# miavita.net
KiCad netlist of a schematic drawn in EAGLE
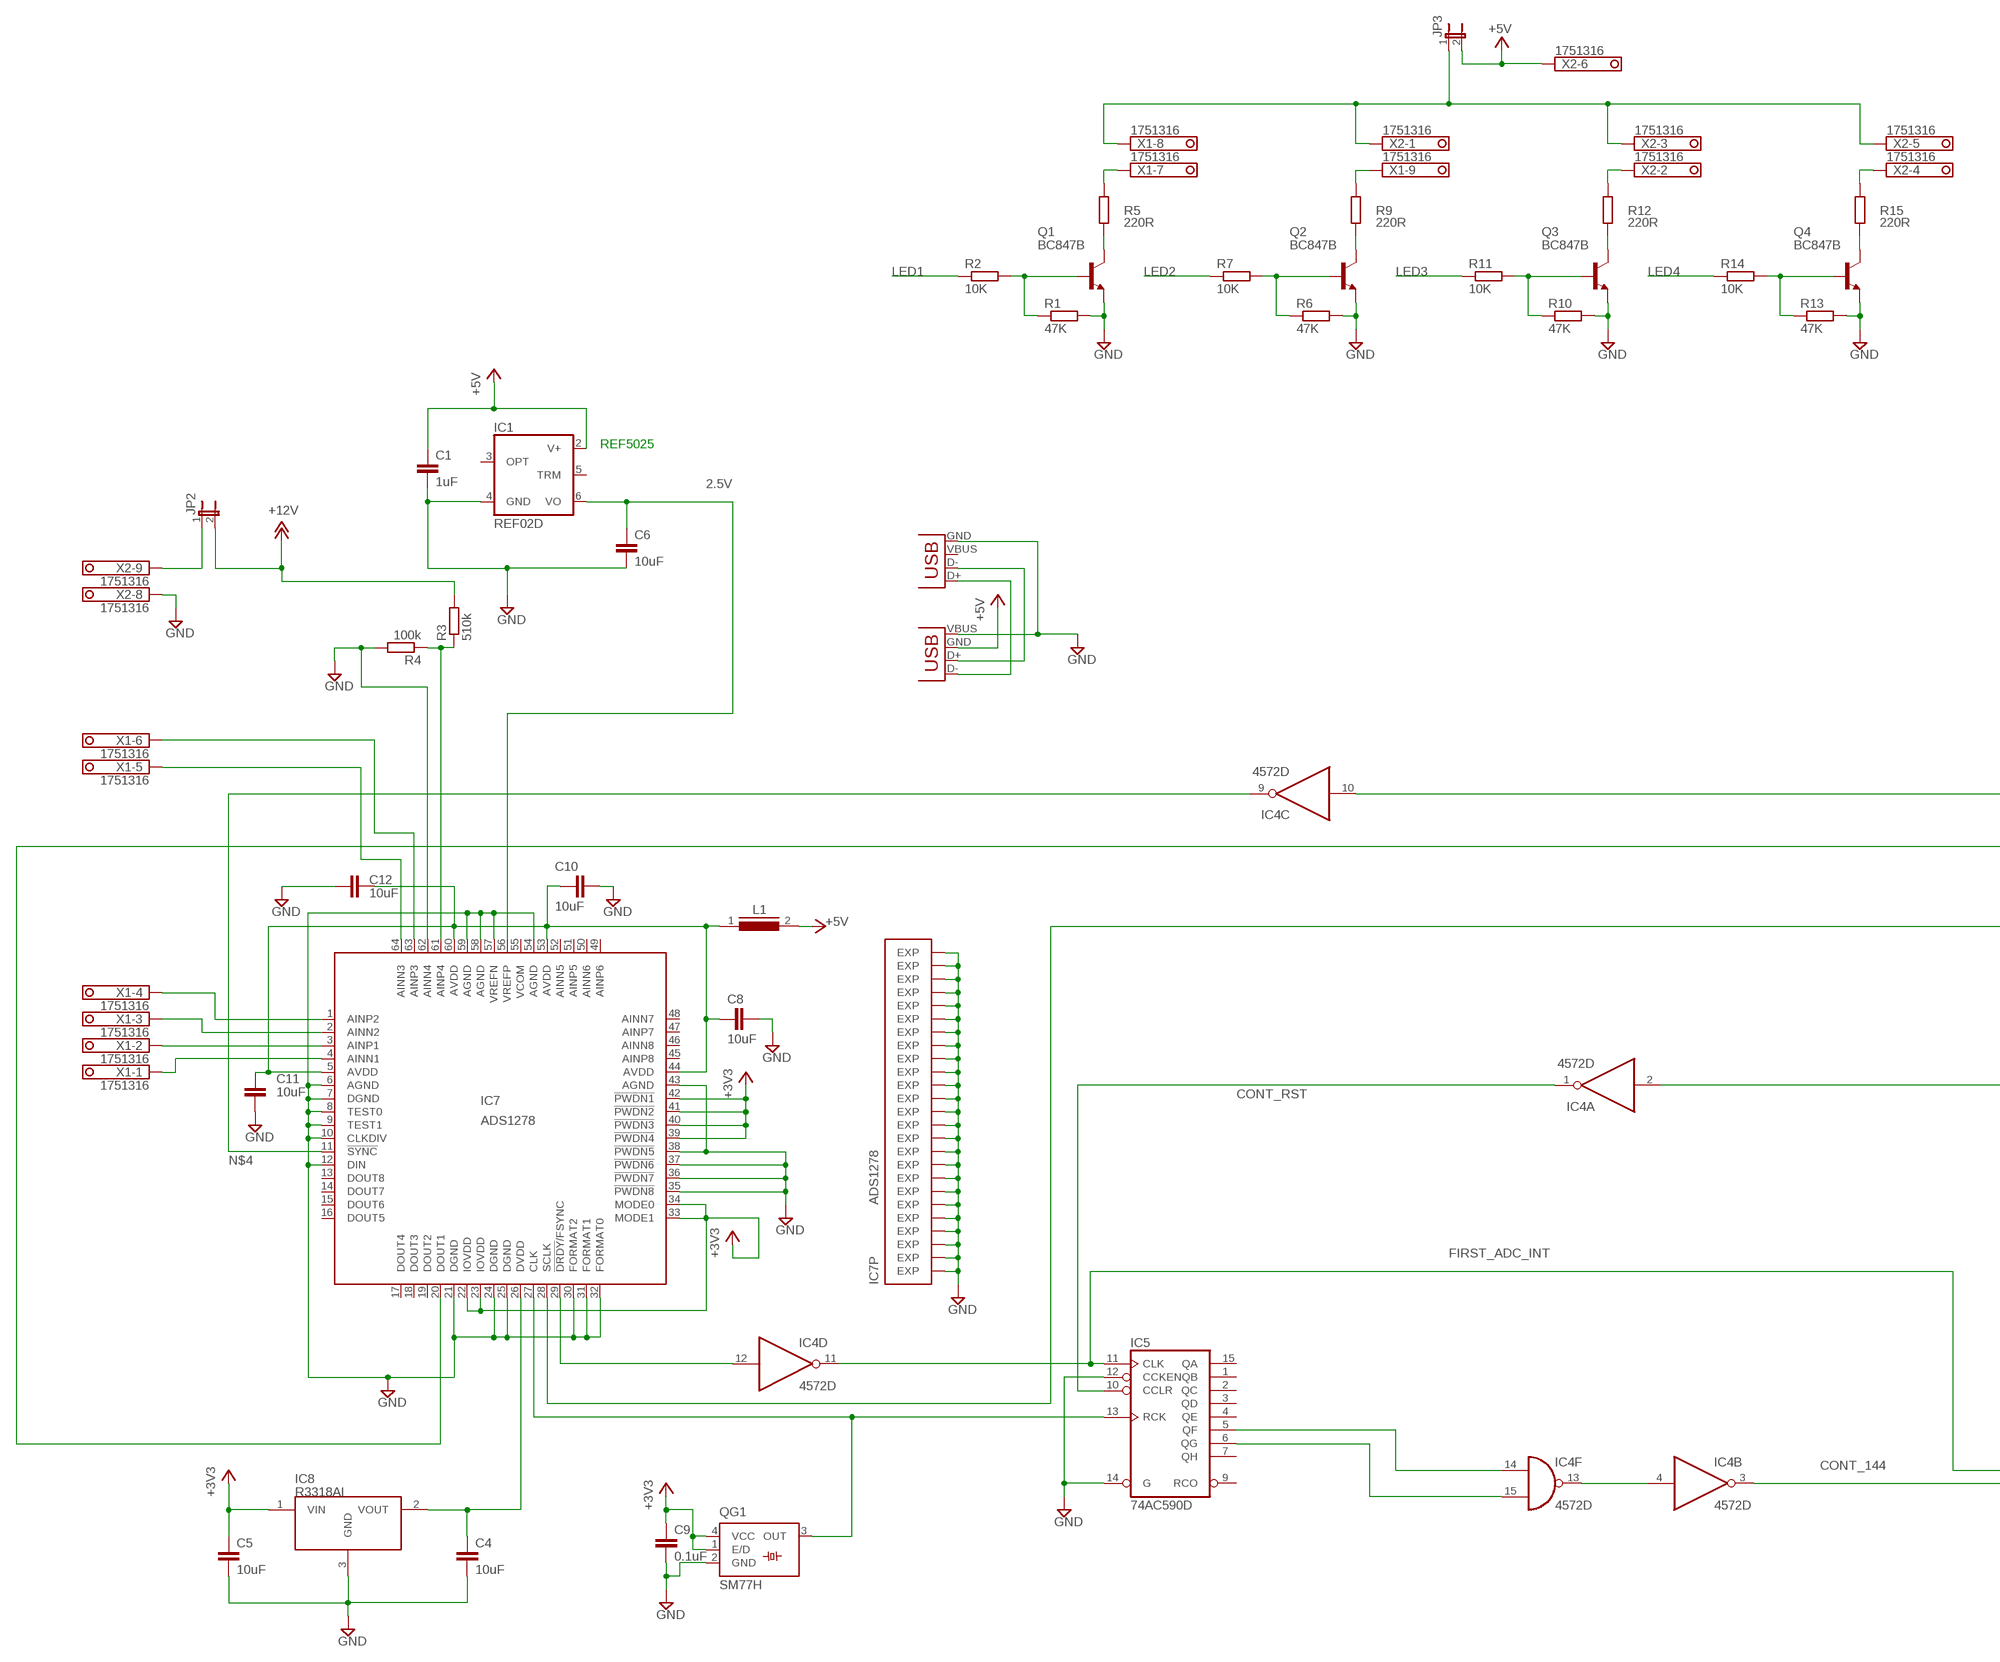
[diagram p0: schematic, sheet 1, part 1 of 2]
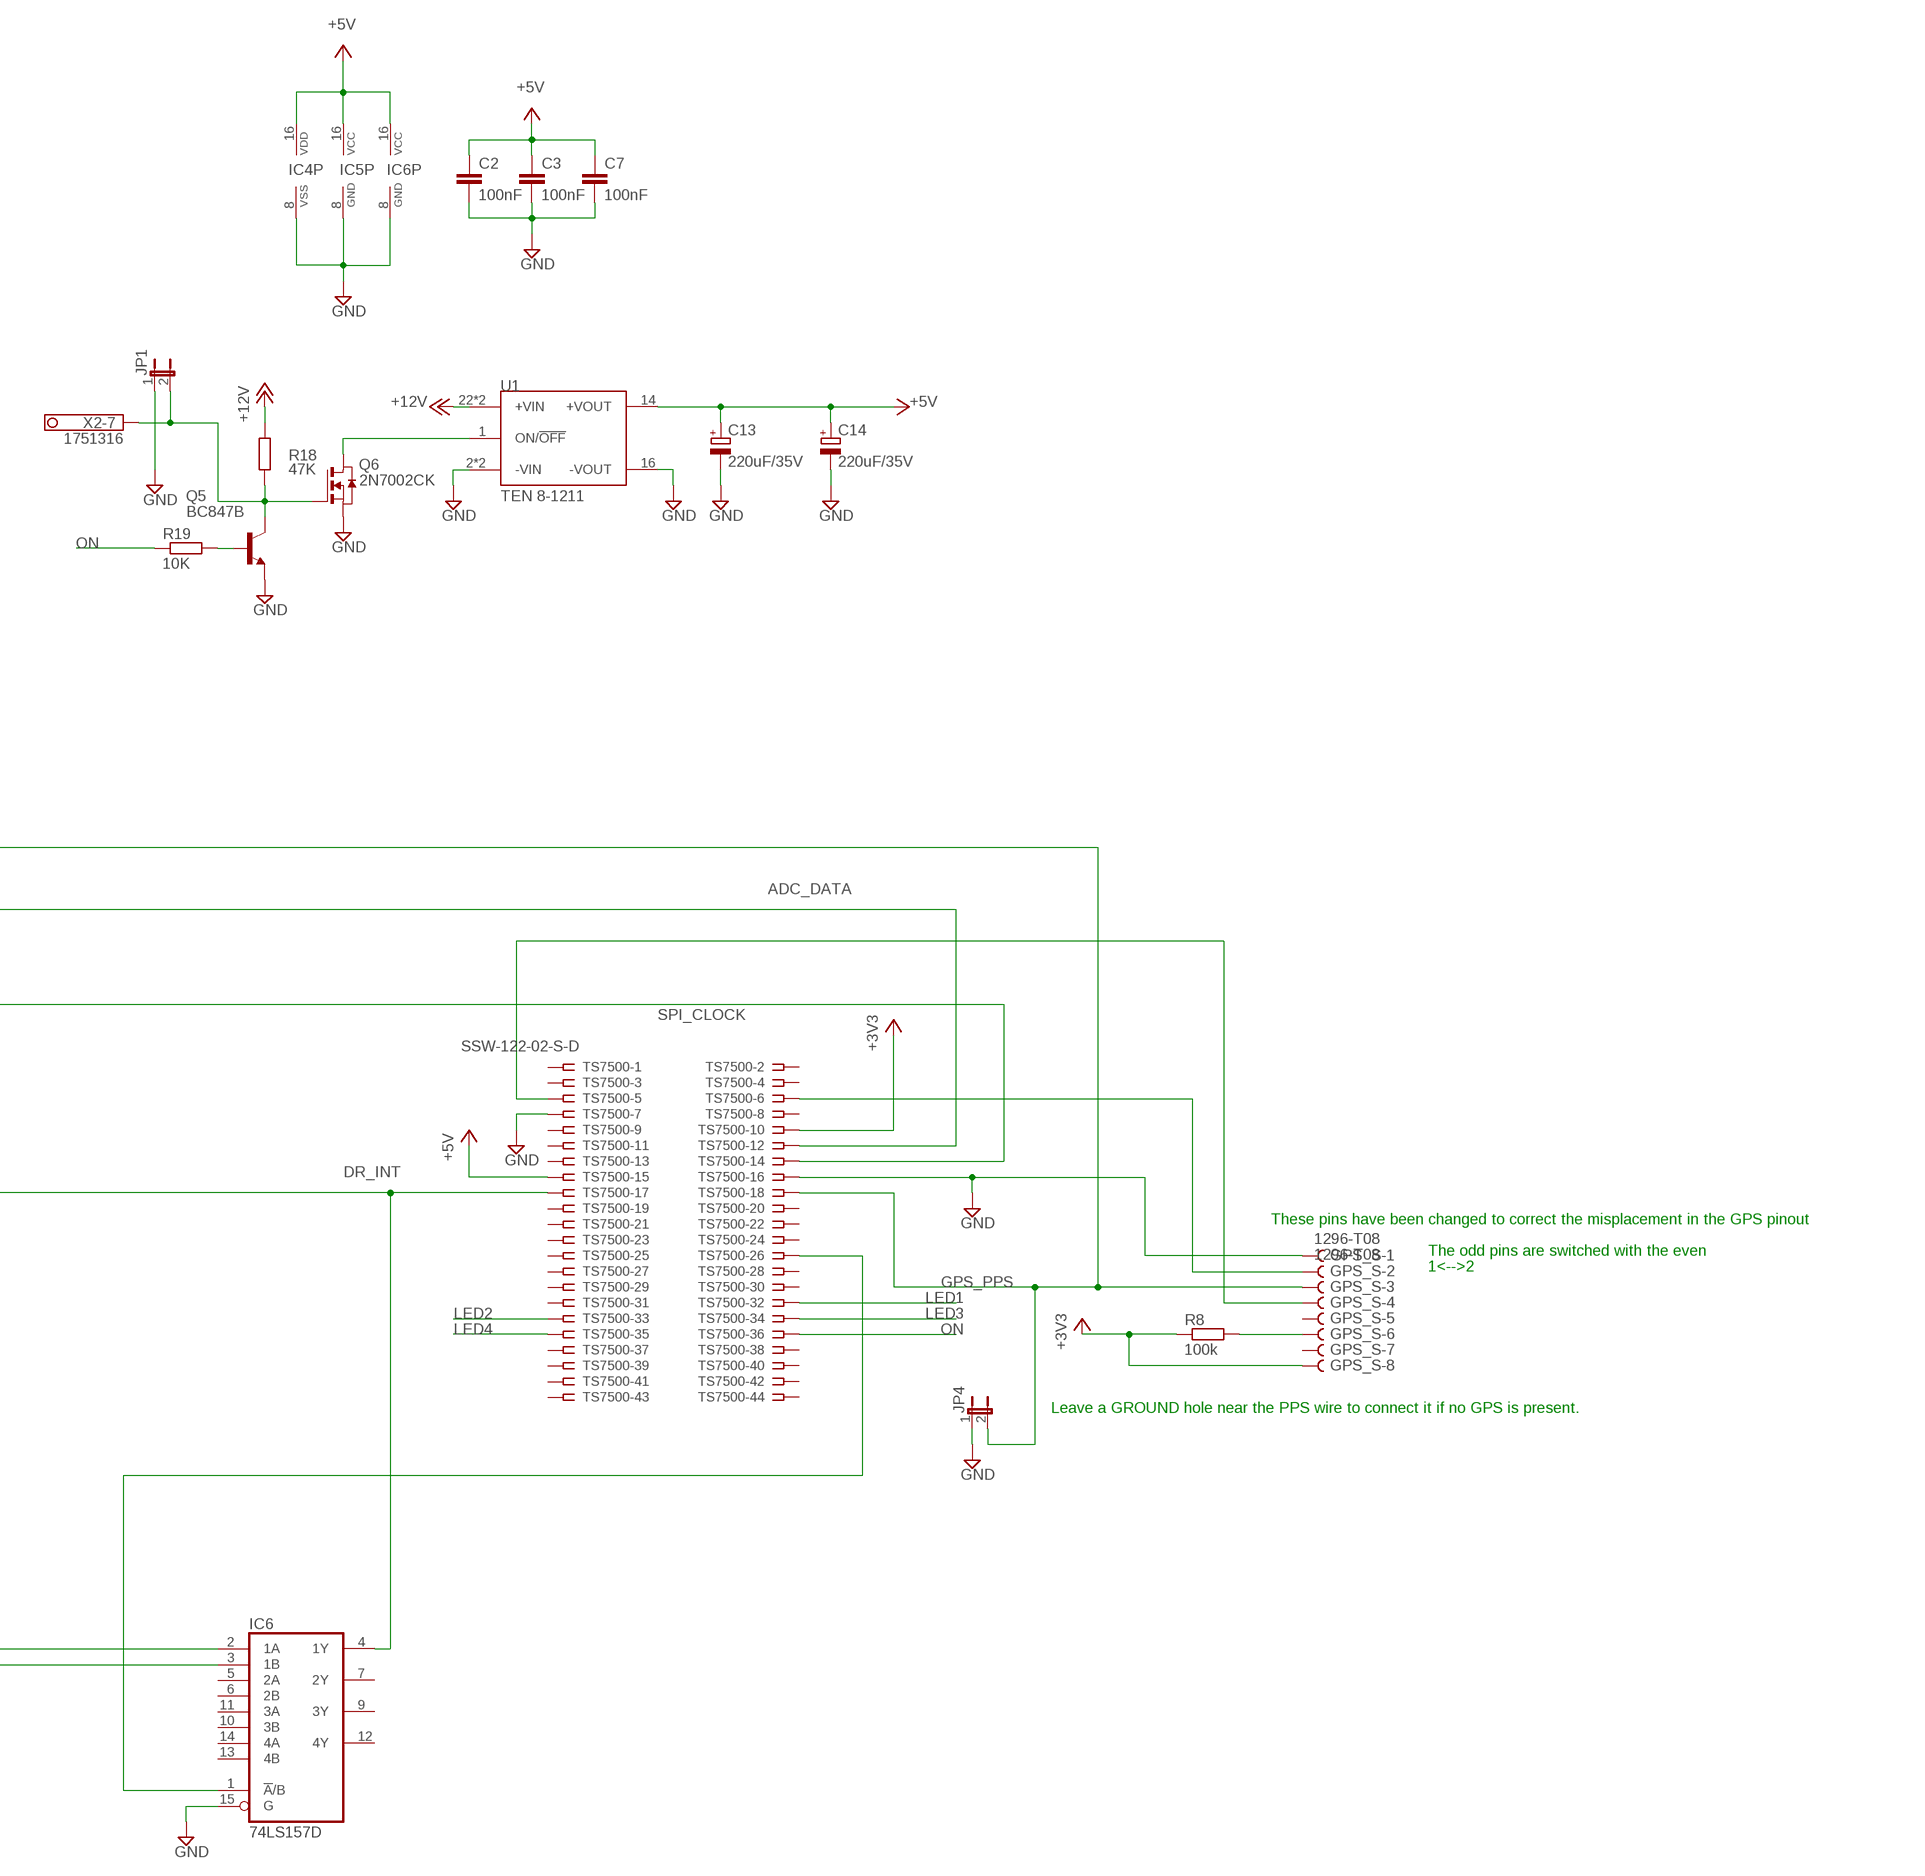
[diagram p1: schematic, sheet 1, part 2 of 2]

(export (version "E")
  (design (tool "Eeschema 10.0.6"))
  (components
    (comp (ref "C1")
      (value "1uF")
      (footprint "eagle-import:C0603")
      (libsource (lib "eagle-import") (part "C-EUC0603"))
    )
    (comp (ref "C2")
      (value "100nF")
      (footprint "eagle-import:C0603")
      (libsource (lib "eagle-import") (part "C-EUC0603"))
    )
    (comp (ref "C3")
      (value "100nF")
      (footprint "eagle-import:C0603")
      (libsource (lib "eagle-import") (part "C-EUC0603"))
    )
    (comp (ref "C4")
      (value "10uF")
      (footprint "eagle-import:C1210")
      (libsource (lib "eagle-import") (part "C-EUC1210"))
    )
    (comp (ref "C5")
      (value "10uF")
      (footprint "eagle-import:C1210")
      (libsource (lib "eagle-import") (part "C-EUC1210"))
    )
    (comp (ref "C6")
      (value "10uF")
      (footprint "eagle-import:C1210")
      (libsource (lib "eagle-import") (part "C-EUC1210"))
    )
    (comp (ref "C7")
      (value "100nF")
      (footprint "eagle-import:C0603")
      (libsource (lib "eagle-import") (part "C-EUC0603"))
    )
    (comp (ref "C8")
      (value "10uF")
      (footprint "eagle-import:C0805")
      (libsource (lib "eagle-import") (part "C-EUC0805"))
    )
    (comp (ref "C9")
      (value "0.1uF")
      (footprint "eagle-import:C0603")
      (libsource (lib "eagle-import") (part "C-EUC0603"))
    )
    (comp (ref "C10")
      (value "10uF")
      (footprint "eagle-import:C0805")
      (libsource (lib "eagle-import") (part "C-EUC0805"))
    )
    (comp (ref "C11")
      (value "10uF")
      (footprint "eagle-import:C0805")
      (libsource (lib "eagle-import") (part "C-EUC0805"))
    )
    (comp (ref "C12")
      (value "10uF")
      (footprint "eagle-import:C0805")
      (libsource (lib "eagle-import") (part "C-EUC0805"))
    )
    (comp (ref "C13")
      (value "220uF/35V")
      (footprint "eagle-import:UD-10X10_NICHICON")
      (libsource (lib "eagle-import") (part "CPOL-EUUD-10X10"))
    )
    (comp (ref "C14")
      (value "220uF/35V")
      (footprint "eagle-import:UD-10X10_NICHICON")
      (libsource (lib "eagle-import") (part "CPOL-EUUD-10X10"))
    )
    (comp (ref "GPS_S")
      (value "1296-T08")
      (footprint "eagle-import:1296-08")
      (libsource (lib "eagle-import") (part "1296-T08"))
    )
    (comp (ref "IC1")
      (value "REF02D")
      (footprint "eagle-import:SO08")
      (libsource (lib "eagle-import") (part "REF02D"))
    )
    (comp (ref "IC4")
      (value "4572D")
      (footprint "eagle-import:SO16")
      (libsource (lib "eagle-import") (part "4572D"))
    )
    (comp (ref "IC5")
      (value "74AC590D")
      (footprint "eagle-import:SO16")
      (libsource (lib "eagle-import") (part "74590DAC"))
    )
    (comp (ref "IC6")
      (value "74LS157D")
      (footprint "eagle-import:SO16")
      (libsource (lib "eagle-import") (part "74157DLS"))
    )
    (comp (ref "IC7")
      (value "ADS1278")
      (footprint "eagle-import:HTQFP-64-PAP")
      (fields (field (name "MPN") "ADS1278IPAPT"))
      (libsource (lib "eagle-import") (part "ADS1278"))
    )
    (comp (ref "IC8")
      (value "R3318AI")
      (footprint "eagle-import:SOT23")
      (libsource (lib "eagle-import") (part "MCP1525TTT-I/"))
    )
    (comp (ref "JP1")
      (value "JP1E")
      (footprint "eagle-import:JP1")
      (libsource (lib "eagle-import") (part "JP1E"))
    )
    (comp (ref "JP2")
      (value "JP1E")
      (footprint "eagle-import:JP1")
      (libsource (lib "eagle-import") (part "JP1E"))
    )
    (comp (ref "JP3")
      (value "JP1E")
      (footprint "eagle-import:JP1")
      (libsource (lib "eagle-import") (part "JP1E"))
    )
    (comp (ref "JP4")
      (value "JP1E")
      (footprint "eagle-import:JP1")
      (libsource (lib "eagle-import") (part "JP1E"))
    )
    (comp (ref "L1")
      (value "FAIR-RITE_2506031027Y0")
      (footprint "eagle-import:L0603")
      (libsource (lib "eagle-import") (part "FAIR-RITE_251027Y00603"))
    )
    (comp (ref "Q1")
      (value "BC847B")
      (footprint "eagle-import:SOT23")
      (libsource (lib "eagle-import") (part "BC847SMDBLT1"))
    )
    (comp (ref "Q2")
      (value "BC847B")
      (footprint "eagle-import:SOT23")
      (libsource (lib "eagle-import") (part "BC847SMDBLT1"))
    )
    (comp (ref "Q3")
      (value "BC847B")
      (footprint "eagle-import:SOT23")
      (libsource (lib "eagle-import") (part "BC847SMDBLT1"))
    )
    (comp (ref "Q4")
      (value "BC847B")
      (footprint "eagle-import:SOT23")
      (libsource (lib "eagle-import") (part "BC847SMDBLT1"))
    )
    (comp (ref "Q5")
      (value "BC847B")
      (footprint "eagle-import:SOT23")
      (libsource (lib "eagle-import") (part "BC847SMDBLT1"))
    )
    (comp (ref "Q6")
      (value "2N7002CK")
      (footprint "eagle-import:SOT23")
      (libsource (lib "eagle-import") (part "2N7002CK"))
    )
    (comp (ref "QG1")
      (value "SM77H")
      (footprint "eagle-import:SM77H")
      (libsource (lib "eagle-import") (part "SM77H"))
    )
    (comp (ref "R1")
      (value "47K")
      (footprint "eagle-import:R0603")
      (libsource (lib "eagle-import") (part "R-EU_R0603"))
    )
    (comp (ref "R2")
      (value "10K")
      (footprint "eagle-import:R0603")
      (libsource (lib "eagle-import") (part "R-EU_R0603"))
    )
    (comp (ref "R3")
      (value "510k")
      (footprint "eagle-import:R0603")
      (libsource (lib "eagle-import") (part "R-EU_R0603"))
    )
    (comp (ref "R4")
      (value "100k")
      (footprint "eagle-import:R0603")
      (libsource (lib "eagle-import") (part "R-EU_R0603"))
    )
    (comp (ref "R5")
      (value "220R")
      (footprint "eagle-import:R0603")
      (libsource (lib "eagle-import") (part "R-EU_R0603"))
    )
    (comp (ref "R6")
      (value "47K")
      (footprint "eagle-import:R0603")
      (libsource (lib "eagle-import") (part "R-EU_R0603"))
    )
    (comp (ref "R7")
      (value "10K")
      (footprint "eagle-import:R0603")
      (libsource (lib "eagle-import") (part "R-EU_R0603"))
    )
    (comp (ref "R8")
      (value "100k")
      (footprint "eagle-import:R0603")
      (libsource (lib "eagle-import") (part "R-EU_R0603"))
    )
    (comp (ref "R9")
      (value "220R")
      (footprint "eagle-import:R0603")
      (libsource (lib "eagle-import") (part "R-EU_R0603"))
    )
    (comp (ref "R10")
      (value "47K")
      (footprint "eagle-import:R0603")
      (libsource (lib "eagle-import") (part "R-EU_R0603"))
    )
    (comp (ref "R11")
      (value "10K")
      (footprint "eagle-import:R0603")
      (libsource (lib "eagle-import") (part "R-EU_R0603"))
    )
    (comp (ref "R12")
      (value "220R")
      (footprint "eagle-import:R0603")
      (libsource (lib "eagle-import") (part "R-EU_R0603"))
    )
    (comp (ref "R13")
      (value "47K")
      (footprint "eagle-import:R0603")
      (libsource (lib "eagle-import") (part "R-EU_R0603"))
    )
    (comp (ref "R14")
      (value "10K")
      (footprint "eagle-import:R0603")
      (libsource (lib "eagle-import") (part "R-EU_R0603"))
    )
    (comp (ref "R15")
      (value "220R")
      (footprint "eagle-import:R0603")
      (libsource (lib "eagle-import") (part "R-EU_R0603"))
    )
    (comp (ref "R18")
      (value "47K")
      (footprint "eagle-import:R0603")
      (libsource (lib "eagle-import") (part "R-EU_R0603"))
    )
    (comp (ref "R19")
      (value "10K")
      (footprint "eagle-import:R0603")
      (libsource (lib "eagle-import") (part "R-EU_R0603"))
    )
    (comp (ref "TS7500")
      (value "SSW-122-02-S-D")
      (footprint "eagle-import:SSW-122-02-S-D")
      (libsource (lib "eagle-import") (part "SSW-122-02-S-D"))
    )
    (comp (ref "U1")
      (value "TEN 8-1211")
      (footprint "eagle-import:TRACOPOWER_TEN-8-SERIES")
      (libsource (lib "eagle-import") (part "TRACOPOWER_TEN-8-1211"))
    )
    (comp (ref "USBA")
      (value "USB-A-H")
      (footprint "eagle-import:USB-A-H")
      (libsource (lib "eagle-import") (part "USB-A-H"))
    )
    (comp (ref "USBB")
      (value "USBPTH")
      (footprint "eagle-import:USB-B-PTH")
      (libsource (lib "eagle-import") (part "USBPTH"))
    )
    (comp (ref "X1")
      (value "1751316")
      (footprint "eagle-import:1751316")
      (libsource (lib "eagle-import") (part "1751316"))
    )
    (comp (ref "X2")
      (value "1751316")
      (footprint "eagle-import:1751316")
      (libsource (lib "eagle-import") (part "1751316"))
    )
  )
  (nets
    (net (code "1") (name "+3V3") (class "Default")
      (node (ref "C5") (pin "1") (pinfunction "1_1") (pintype "passive"))
      (node (ref "C9") (pin "1") (pinfunction "1_1") (pintype "passive"))
      (node (ref "GPS_S") (pin "8") (pinfunction "B_8") (pintype "passive"))
      (node (ref "IC7") (pin "22") (pinfunction "IOVDD_22") (pintype "power_in"))
      (node (ref "IC7") (pin "23") (pinfunction "IOVDD_23") (pintype "power_in"))
      (node (ref "IC7") (pin "33") (pinfunction "MODE1_33") (pintype "input"))
      (node (ref "IC7") (pin "34") (pinfunction "MODE0_34") (pintype "input"))
      (node (ref "IC7") (pin "39") (pinfunction "~{PWDN4}_39") (pintype "input"))
      (node (ref "IC7") (pin "40") (pinfunction "~{PWDN3}_40") (pintype "input"))
      (node (ref "IC7") (pin "41") (pinfunction "~{PWDN2}_41") (pintype "input"))
      (node (ref "IC7") (pin "42") (pinfunction "~{PWDN1}_42") (pintype "input"))
      (node (ref "IC8") (pin "1") (pinfunction "VIN_1") (pintype "power_in"))
      (node (ref "QG1") (pin "1") (pinfunction "E/D_1") (pintype "input"))
      (node (ref "QG1") (pin "4") (pinfunction "VCC_4") (pintype "power_in"))
      (node (ref "R8") (pin "1") (pinfunction "1_1") (pintype "passive"))
      (node (ref "TS7500") (pin "10") (pinfunction "1_10") (pintype "passive"))
    )
    (net (code "2") (name "+5V") (class "Default")
      (node (ref "C1") (pin "1") (pinfunction "1_1") (pintype "passive"))
      (node (ref "C13") (pin "+") (pinfunction "+_+") (pintype "passive"))
      (node (ref "C14") (pin "+") (pinfunction "+_+") (pintype "passive"))
      (node (ref "C2") (pin "1") (pinfunction "1_1") (pintype "passive"))
      (node (ref "C3") (pin "1") (pinfunction "1_1") (pintype "passive"))
      (node (ref "C7") (pin "1") (pinfunction "1_1") (pintype "passive"))
      (node (ref "IC1") (pin "2") (pinfunction "V+_2") (pintype "power_in"))
      (node (ref "IC4") (pin "16") (pinfunction "VDD_16") (pintype "power_in"))
      (node (ref "IC5") (pin "16") (pinfunction "VCC_16") (pintype "power_in"))
      (node (ref "IC6") (pin "16") (pinfunction "VCC_16") (pintype "power_in"))
      (node (ref "JP3") (pin "2") (pinfunction "2_2") (pintype "passive"))
      (node (ref "L1") (pin "2") (pinfunction "2_2") (pintype "passive"))
      (node (ref "TS7500") (pin "15") (pinfunction "1_15") (pintype "passive"))
      (node (ref "U1") (pin "14") (pinfunction "+VOUT_14") (pintype "bidirectional"))
      (node (ref "USBA") (pin "GND") (pinfunction "VBUS_GND") (pintype "bidirectional"))
      (node (ref "X2") (pin "6") (pinfunction "K_6") (pintype "passive"))
    )
    (net (code "3") (name "+12V") (class "Default")
      (node (ref "JP2") (pin "2") (pinfunction "2_2") (pintype "passive"))
      (node (ref "R18") (pin "1") (pinfunction "1_1") (pintype "passive"))
      (node (ref "R3") (pin "2") (pinfunction "2_2") (pintype "passive"))
      (node (ref "U1") (pin "22") (pinfunction "+VIN_22") (pintype "power_in"))
      (node (ref "U1") (pin "23") (pinfunction "+VIN_23") (pintype "power_in"))
    )
    (net (code "4") (name "/2.5V") (class "Default")
      (node (ref "C6") (pin "1") (pinfunction "1_1") (pintype "passive"))
      (node (ref "IC1") (pin "6") (pinfunction "VO_6") (pintype "output"))
      (node (ref "IC7") (pin "56") (pinfunction "VREFP_56") (pintype "input"))
    )
    (net (code "5") (name "/ADC_DATA") (class "Default")
      (node (ref "IC7") (pin "20") (pinfunction "DOUT1_20") (pintype "output"))
      (node (ref "TS7500") (pin "12") (pinfunction "1_12") (pintype "passive"))
    )
    (net (code "6") (name "/CONT_144") (class "Default")
      (node (ref "IC4") (pin "3") (pinfunction "O_3") (pintype "output"))
      (node (ref "IC6") (pin "3") (pinfunction "1B_3") (pintype "input"))
    )
    (net (code "7") (name "/CONT_RST") (class "Default")
      (node (ref "IC4") (pin "1") (pinfunction "O_1") (pintype "output"))
      (node (ref "IC5") (pin "10") (pinfunction "CCLR_10") (pintype "input"))
    )
    (net (code "8") (name "/DR_INT") (class "Default")
      (node (ref "IC4") (pin "2") (pinfunction "I_2") (pintype "input"))
      (node (ref "IC6") (pin "4") (pinfunction "1Y_4") (pintype "output"))
      (node (ref "TS7500") (pin "17") (pinfunction "1_17") (pintype "passive"))
    )
    (net (code "9") (name "/FIRST_ADC_INT") (class "Default")
      (node (ref "IC4") (pin "11") (pinfunction "O_11") (pintype "output"))
      (node (ref "IC5") (pin "11") (pinfunction "CLK_11") (pintype "input"))
      (node (ref "IC6") (pin "2") (pinfunction "1A_2") (pintype "input"))
    )
    (net (code "10") (name "/GPS_PPS") (class "Default")
      (node (ref "GPS_S") (pin "3") (pinfunction "B_3") (pintype "passive"))
      (node (ref "IC4") (pin "10") (pinfunction "I_10") (pintype "input"))
      (node (ref "JP4") (pin "2") (pinfunction "2_2") (pintype "passive"))
      (node (ref "TS7500") (pin "18") (pinfunction "1_18") (pintype "passive"))
    )
    (net (code "11") (name "/LED1") (class "Default")
      (node (ref "R2") (pin "1") (pinfunction "1_1") (pintype "passive"))
      (node (ref "TS7500") (pin "32") (pinfunction "1_32") (pintype "passive"))
    )
    (net (code "12") (name "/LED2") (class "Default")
      (node (ref "R7") (pin "1") (pinfunction "1_1") (pintype "passive"))
      (node (ref "TS7500") (pin "33") (pinfunction "1_33") (pintype "passive"))
    )
    (net (code "13") (name "/LED3") (class "Default")
      (node (ref "R11") (pin "1") (pinfunction "1_1") (pintype "passive"))
      (node (ref "TS7500") (pin "34") (pinfunction "1_34") (pintype "passive"))
    )
    (net (code "14") (name "/LED4") (class "Default")
      (node (ref "R14") (pin "1") (pinfunction "1_1") (pintype "passive"))
      (node (ref "TS7500") (pin "35") (pinfunction "1_35") (pintype "passive"))
    )
    (net (code "15") (name "/N$4") (class "Default")
      (node (ref "IC4") (pin "9") (pinfunction "O_9") (pintype "output"))
      (node (ref "IC7") (pin "11") (pinfunction "~{SYNC}_11") (pintype "input"))
    )
    (net (code "16") (name "/ON") (class "Default")
      (node (ref "R19") (pin "1") (pinfunction "1_1") (pintype "passive"))
      (node (ref "TS7500") (pin "36") (pinfunction "1_36") (pintype "passive"))
    )
    (net (code "17") (name "/SPI_CLOCK") (class "Default")
      (node (ref "IC7") (pin "28") (pinfunction "SCLK_28") (pintype "bidirectional"))
      (node (ref "TS7500") (pin "14") (pinfunction "1_14") (pintype "passive"))
    )
    (net (code "18") (name "GND") (class "Default")
      (node (ref "C1") (pin "2") (pinfunction "2_2") (pintype "passive"))
      (node (ref "C10") (pin "2") (pinfunction "2_2") (pintype "passive"))
      (node (ref "C11") (pin "2") (pinfunction "2_2") (pintype "passive"))
      (node (ref "C12") (pin "2") (pinfunction "2_2") (pintype "passive"))
      (node (ref "C13") (pin "-") (pinfunction "-_-") (pintype "passive"))
      (node (ref "C14") (pin "-") (pinfunction "-_-") (pintype "passive"))
      (node (ref "C2") (pin "2") (pinfunction "2_2") (pintype "passive"))
      (node (ref "C3") (pin "2") (pinfunction "2_2") (pintype "passive"))
      (node (ref "C4") (pin "2") (pinfunction "2_2") (pintype "passive"))
      (node (ref "C5") (pin "2") (pinfunction "2_2") (pintype "passive"))
      (node (ref "C6") (pin "2") (pinfunction "2_2") (pintype "passive"))
      (node (ref "C7") (pin "2") (pinfunction "2_2") (pintype "passive"))
      (node (ref "C8") (pin "2") (pinfunction "2_2") (pintype "passive"))
      (node (ref "C9") (pin "2") (pinfunction "2_2") (pintype "passive"))
      (node (ref "GPS_S") (pin "1") (pinfunction "B_1") (pintype "passive"))
      (node (ref "IC1") (pin "4") (pinfunction "GND_4") (pintype "power_in"))
      (node (ref "IC4") (pin "8") (pinfunction "VSS_8") (pintype "power_in"))
      (node (ref "IC5") (pin "12") (pinfunction "CCKEN_12") (pintype "input"))
      (node (ref "IC5") (pin "14") (pinfunction "G_14") (pintype "input"))
      (node (ref "IC5") (pin "8") (pinfunction "GND_8") (pintype "power_in"))
      (node (ref "IC6") (pin "15") (pinfunction "G_15") (pintype "input"))
      (node (ref "IC6") (pin "8") (pinfunction "GND_8") (pintype "power_in"))
      (node (ref "IC7") (pin "10") (pinfunction "CLKDIV_10") (pintype "input"))
      (node (ref "IC7") (pin "12") (pinfunction "DIN_12") (pintype "input"))
      (node (ref "IC7") (pin "21") (pinfunction "DGND_21") (pintype "power_in"))
      (node (ref "IC7") (pin "24") (pinfunction "DGND_24") (pintype "power_in"))
      (node (ref "IC7") (pin "25") (pinfunction "DGND_25") (pintype "power_in"))
      (node (ref "IC7") (pin "30") (pinfunction "FORMAT2_30") (pintype "input"))
      (node (ref "IC7") (pin "31") (pinfunction "FORMAT1_31") (pintype "input"))
      (node (ref "IC7") (pin "32") (pinfunction "FORMAT0_32") (pintype "input"))
      (node (ref "IC7") (pin "35") (pinfunction "~{PWDN8}_35") (pintype "input"))
      (node (ref "IC7") (pin "36") (pinfunction "~{PWDN7}_36") (pintype "input"))
      (node (ref "IC7") (pin "37") (pinfunction "~{PWDN6}_37") (pintype "input"))
      (node (ref "IC7") (pin "38") (pinfunction "~{PWDN5}_38") (pintype "input"))
      (node (ref "IC7") (pin "43") (pinfunction "AGND_43") (pintype "power_in"))
      (node (ref "IC7") (pin "54") (pinfunction "AGND_54") (pintype "power_in"))
      (node (ref "IC7") (pin "57") (pinfunction "VREFN_57") (pintype "input"))
      (node (ref "IC7") (pin "58") (pinfunction "AGND_58") (pintype "power_in"))
      (node (ref "IC7") (pin "59") (pinfunction "AGND_59") (pintype "power_in"))
      (node (ref "IC7") (pin "6") (pinfunction "AGND_6") (pintype "power_in"))
      (node (ref "IC7") (pin "62") (pinfunction "AINN4_62") (pintype "input"))
      (node (ref "IC7") (pin "7") (pinfunction "DGND_7") (pintype "power_in"))
      (node (ref "IC7") (pin "8") (pinfunction "TEST0_8") (pintype "input"))
      (node (ref "IC7") (pin "9") (pinfunction "TEST1_9") (pintype "input"))
      (node (ref "IC7") (pin "EXP1") (pinfunction "EXP_EXP1") (pintype "passive"))
      (node (ref "IC7") (pin "EXP10") (pinfunction "EXP_EXP10") (pintype "passive"))
      (node (ref "IC7") (pin "EXP11") (pinfunction "EXP_EXP11") (pintype "passive"))
      (node (ref "IC7") (pin "EXP12") (pinfunction "EXP_EXP12") (pintype "passive"))
      (node (ref "IC7") (pin "EXP13") (pinfunction "EXP_EXP13") (pintype "passive"))
      (node (ref "IC7") (pin "EXP14") (pinfunction "EXP_EXP14") (pintype "passive"))
      (node (ref "IC7") (pin "EXP15") (pinfunction "EXP_EXP15") (pintype "passive"))
      (node (ref "IC7") (pin "EXP16") (pinfunction "EXP_EXP16") (pintype "passive"))
      (node (ref "IC7") (pin "EXP17") (pinfunction "EXP_EXP17") (pintype "passive"))
      (node (ref "IC7") (pin "EXP18") (pinfunction "EXP_EXP18") (pintype "passive"))
      (node (ref "IC7") (pin "EXP19") (pinfunction "EXP_EXP19") (pintype "passive"))
      (node (ref "IC7") (pin "EXP2") (pinfunction "EXP_EXP2") (pintype "passive"))
      (node (ref "IC7") (pin "EXP20") (pinfunction "EXP_EXP20") (pintype "passive"))
      (node (ref "IC7") (pin "EXP21") (pinfunction "EXP_EXP21") (pintype "passive"))
      (node (ref "IC7") (pin "EXP22") (pinfunction "EXP_EXP22") (pintype "passive"))
      (node (ref "IC7") (pin "EXP23") (pinfunction "EXP_EXP23") (pintype "passive"))
      (node (ref "IC7") (pin "EXP24") (pinfunction "EXP_EXP24") (pintype "passive"))
      (node (ref "IC7") (pin "EXP25") (pinfunction "EXP_EXP25") (pintype "passive"))
      (node (ref "IC7") (pin "EXP3") (pinfunction "EXP_EXP3") (pintype "passive"))
      (node (ref "IC7") (pin "EXP4") (pinfunction "EXP_EXP4") (pintype "passive"))
      (node (ref "IC7") (pin "EXP5") (pinfunction "EXP_EXP5") (pintype "passive"))
      (node (ref "IC7") (pin "EXP6") (pinfunction "EXP_EXP6") (pintype "passive"))
      (node (ref "IC7") (pin "EXP7") (pinfunction "EXP_EXP7") (pintype "passive"))
      (node (ref "IC7") (pin "EXP8") (pinfunction "EXP_EXP8") (pintype "passive"))
      (node (ref "IC7") (pin "EXP9") (pinfunction "EXP_EXP9") (pintype "passive"))
      (node (ref "IC8") (pin "3") (pinfunction "GND_3") (pintype "power_in"))
      (node (ref "JP1") (pin "1") (pinfunction "1_1") (pintype "passive"))
      (node (ref "JP4") (pin "1") (pinfunction "1_1") (pintype "passive"))
      (node (ref "Q1") (pin "2") (pinfunction "E_2") (pintype "passive"))
      (node (ref "Q2") (pin "2") (pinfunction "E_2") (pintype "passive"))
      (node (ref "Q3") (pin "2") (pinfunction "E_2") (pintype "passive"))
      (node (ref "Q4") (pin "2") (pinfunction "E_2") (pintype "passive"))
      (node (ref "Q5") (pin "2") (pinfunction "E_2") (pintype "passive"))
      (node (ref "Q6") (pin "2") (pinfunction "S_2") (pintype "passive"))
      (node (ref "QG1") (pin "2") (pinfunction "GND_2") (pintype "power_in"))
      (node (ref "R1") (pin "2") (pinfunction "2_2") (pintype "passive"))
      (node (ref "R10") (pin "2") (pinfunction "2_2") (pintype "passive"))
      (node (ref "R13") (pin "2") (pinfunction "2_2") (pintype "passive"))
      (node (ref "R4") (pin "2") (pinfunction "2_2") (pintype "passive"))
      (node (ref "R6") (pin "2") (pinfunction "2_2") (pintype "passive"))
      (node (ref "TS7500") (pin "16") (pinfunction "1_16") (pintype "passive"))
      (node (ref "TS7500") (pin "7") (pinfunction "1_7") (pintype "passive"))
      (node (ref "U1") (pin "16") (pinfunction "-VOUT_16") (pintype "bidirectional"))
      (node (ref "U1") (pin "2") (pinfunction "-VIN_2") (pintype "bidirectional"))
      (node (ref "U1") (pin "3") (pinfunction "-VIN_3") (pintype "bidirectional"))
      (node (ref "USBA") (pin "VBUS") (pinfunction "GND_VBUS") (pintype "bidirectional"))
      (node (ref "USBB") (pin "GND") (pinfunction "GND_GND") (pintype "bidirectional"))
      (node (ref "X2") (pin "8") (pinfunction "K_8") (pintype "passive"))
    )
    (net (code "19") (name "Net-(C10-Pad1)") (class "Default")
      (node (ref "C10") (pin "1") (pinfunction "1_1") (pintype "passive"))
      (node (ref "C11") (pin "1") (pinfunction "1_1") (pintype "passive"))
      (node (ref "C12") (pin "1") (pinfunction "1_1") (pintype "passive"))
      (node (ref "C8") (pin "1") (pinfunction "1_1") (pintype "passive"))
      (node (ref "IC7") (pin "44") (pinfunction "AVDD_44") (pintype "power_in"))
      (node (ref "IC7") (pin "5") (pinfunction "AVDD_5") (pintype "power_in"))
      (node (ref "IC7") (pin "53") (pinfunction "AVDD_53") (pintype "power_in"))
      (node (ref "IC7") (pin "60") (pinfunction "AVDD_60") (pintype "power_in"))
      (node (ref "L1") (pin "1") (pinfunction "1_1") (pintype "passive"))
    )
    (net (code "20") (name "Net-(GPS_SB-B)") (class "Default")
      (node (ref "GPS_S") (pin "2") (pinfunction "B_2") (pintype "passive"))
      (node (ref "TS7500") (pin "6") (pinfunction "1_6") (pintype "passive"))
    )
    (net (code "21") (name "Net-(GPS_SD-B)") (class "Default")
      (node (ref "GPS_S") (pin "4") (pinfunction "B_4") (pintype "passive"))
      (node (ref "TS7500") (pin "5") (pinfunction "1_5") (pintype "passive"))
    )
    (net (code "22") (name "Net-(GPS_SF-B)") (class "Default")
      (node (ref "GPS_S") (pin "6") (pinfunction "B_6") (pintype "passive"))
      (node (ref "R8") (pin "2") (pinfunction "2_2") (pintype "passive"))
    )
    (net (code "23") (name "Net-(IC4B-I)") (class "Default")
      (node (ref "IC4") (pin "13") (pinfunction "O_13") (pintype "output"))
      (node (ref "IC4") (pin "4") (pinfunction "I_4") (pintype "input"))
    )
    (net (code "24") (name "Net-(IC4D-I)") (class "Default")
      (node (ref "IC4") (pin "12") (pinfunction "I_12") (pintype "input"))
      (node (ref "IC7") (pin "29") (pinfunction "~{DRDY}/FSYNC_29") (pintype "bidirectional"))
    )
    (net (code "25") (name "Net-(IC4F-I0)") (class "Default")
      (node (ref "IC4") (pin "14") (pinfunction "I0_14") (pintype "input"))
      (node (ref "IC5") (pin "5") (pinfunction "QF_5") (pintype "tri_state"))
    )
    (net (code "26") (name "Net-(IC4F-I1)") (class "Default")
      (node (ref "IC4") (pin "15") (pinfunction "I1_15") (pintype "input"))
      (node (ref "IC5") (pin "6") (pinfunction "QG_6") (pintype "tri_state"))
    )
    (net (code "27") (name "Net-(IC5A-RCK)") (class "Default")
      (node (ref "IC5") (pin "13") (pinfunction "RCK_13") (pintype "input"))
      (node (ref "IC7") (pin "27") (pinfunction "CLK_27") (pintype "input"))
      (node (ref "QG1") (pin "3") (pinfunction "OUT_3") (pintype "output"))
    )
    (net (code "28") (name "Net-(IC6A-~{A}{slash}B)") (class "Default")
      (node (ref "IC6") (pin "1") (pinfunction "~{A}/B_1") (pintype "input"))
      (node (ref "TS7500") (pin "26") (pinfunction "1_26") (pintype "passive"))
    )
    (net (code "29") (name "Net-(IC7A-AINN1)") (class "Default")
      (node (ref "IC7") (pin "4") (pinfunction "AINN1_4") (pintype "input"))
      (node (ref "X1") (pin "1") (pinfunction "K_1") (pintype "passive"))
    )
    (net (code "30") (name "Net-(IC7A-AINN2)") (class "Default")
      (node (ref "IC7") (pin "2") (pinfunction "AINN2_2") (pintype "input"))
      (node (ref "X1") (pin "3") (pinfunction "K_3") (pintype "passive"))
    )
    (net (code "31") (name "Net-(IC7A-AINN3)") (class "Default")
      (node (ref "IC7") (pin "64") (pinfunction "AINN3_64") (pintype "input"))
      (node (ref "X1") (pin "5") (pinfunction "K_5") (pintype "passive"))
    )
    (net (code "32") (name "Net-(IC7A-AINP1)") (class "Default")
      (node (ref "IC7") (pin "3") (pinfunction "AINP1_3") (pintype "input"))
      (node (ref "X1") (pin "2") (pinfunction "K_2") (pintype "passive"))
    )
    (net (code "33") (name "Net-(IC7A-AINP2)") (class "Default")
      (node (ref "IC7") (pin "1") (pinfunction "AINP2_1") (pintype "input"))
      (node (ref "X1") (pin "4") (pinfunction "K_4") (pintype "passive"))
    )
    (net (code "34") (name "Net-(IC7A-AINP3)") (class "Default")
      (node (ref "IC7") (pin "63") (pinfunction "AINP3_63") (pintype "input"))
      (node (ref "X1") (pin "6") (pinfunction "K_6") (pintype "passive"))
    )
    (net (code "35") (name "Net-(IC7A-AINP4)") (class "Default")
      (node (ref "IC7") (pin "61") (pinfunction "AINP4_61") (pintype "input"))
      (node (ref "R3") (pin "1") (pinfunction "1_1") (pintype "passive"))
      (node (ref "R4") (pin "1") (pinfunction "1_1") (pintype "passive"))
    )
    (net (code "36") (name "Net-(IC7A-DVDD)") (class "Default")
      (node (ref "C4") (pin "1") (pinfunction "1_1") (pintype "passive"))
      (node (ref "IC7") (pin "26") (pinfunction "DVDD_26") (pintype "power_in"))
      (node (ref "IC8") (pin "2") (pinfunction "VOUT_2") (pintype "power_in"))
    )
    (net (code "37") (name "Net-(Q1-B)") (class "Default")
      (node (ref "Q1") (pin "1") (pinfunction "B_1") (pintype "passive"))
      (node (ref "R1") (pin "1") (pinfunction "1_1") (pintype "passive"))
      (node (ref "R2") (pin "2") (pinfunction "2_2") (pintype "passive"))
    )
    (net (code "38") (name "Net-(Q1-C)") (class "Default")
      (node (ref "Q1") (pin "3") (pinfunction "C_3") (pintype "passive"))
      (node (ref "R5") (pin "1") (pinfunction "1_1") (pintype "passive"))
    )
    (net (code "39") (name "Net-(Q2-B)") (class "Default")
      (node (ref "Q2") (pin "1") (pinfunction "B_1") (pintype "passive"))
      (node (ref "R6") (pin "1") (pinfunction "1_1") (pintype "passive"))
      (node (ref "R7") (pin "2") (pinfunction "2_2") (pintype "passive"))
    )
    (net (code "40") (name "Net-(Q2-C)") (class "Default")
      (node (ref "Q2") (pin "3") (pinfunction "C_3") (pintype "passive"))
      (node (ref "R9") (pin "1") (pinfunction "1_1") (pintype "passive"))
    )
    (net (code "41") (name "Net-(Q3-B)") (class "Default")
      (node (ref "Q3") (pin "1") (pinfunction "B_1") (pintype "passive"))
      (node (ref "R10") (pin "1") (pinfunction "1_1") (pintype "passive"))
      (node (ref "R11") (pin "2") (pinfunction "2_2") (pintype "passive"))
    )
    (net (code "42") (name "Net-(Q3-C)") (class "Default")
      (node (ref "Q3") (pin "3") (pinfunction "C_3") (pintype "passive"))
      (node (ref "R12") (pin "1") (pinfunction "1_1") (pintype "passive"))
    )
    (net (code "43") (name "Net-(Q4-B)") (class "Default")
      (node (ref "Q4") (pin "1") (pinfunction "B_1") (pintype "passive"))
      (node (ref "R13") (pin "1") (pinfunction "1_1") (pintype "passive"))
      (node (ref "R14") (pin "2") (pinfunction "2_2") (pintype "passive"))
    )
    (net (code "44") (name "Net-(Q4-C)") (class "Default")
      (node (ref "Q4") (pin "3") (pinfunction "C_3") (pintype "passive"))
      (node (ref "R15") (pin "1") (pinfunction "1_1") (pintype "passive"))
    )
    (net (code "45") (name "Net-(Q5-B)") (class "Default")
      (node (ref "Q5") (pin "1") (pinfunction "B_1") (pintype "passive"))
      (node (ref "R19") (pin "2") (pinfunction "2_2") (pintype "passive"))
    )
    (net (code "46") (name "Net-(Q5-C)") (class "Default")
      (node (ref "JP1") (pin "2") (pinfunction "2_2") (pintype "passive"))
      (node (ref "Q5") (pin "3") (pinfunction "C_3") (pintype "passive"))
      (node (ref "Q6") (pin "1") (pinfunction "G_1") (pintype "passive"))
      (node (ref "R18") (pin "2") (pinfunction "2_2") (pintype "passive"))
      (node (ref "X2") (pin "7") (pinfunction "K_7") (pintype "passive"))
    )
    (net (code "47") (name "Net-(Q6-D)") (class "Default")
      (node (ref "Q6") (pin "3") (pinfunction "D_3") (pintype "passive"))
      (node (ref "U1") (pin "1") (pinfunction "ON/~{OFF}_1") (pintype "bidirectional"))
    )
    (net (code "48") (name "Net-(USBA-D+)") (class "Default")
      (node (ref "USBA") (pin "D-") (pinfunction "D+_D-") (pintype "bidirectional"))
      (node (ref "USBB") (pin "D+") (pinfunction "D+_D+") (pintype "bidirectional"))
    )
    (net (code "49") (name "Net-(USBA-D-)") (class "Default")
      (node (ref "USBA") (pin "D+") (pinfunction "D-_D+") (pintype "bidirectional"))
      (node (ref "USBB") (pin "D-") (pinfunction "D-_D-") (pintype "bidirectional"))
    )
    (net (code "50") (name "Net-(X1G-K)") (class "Default")
      (node (ref "R5") (pin "2") (pinfunction "2_2") (pintype "passive"))
      (node (ref "X1") (pin "7") (pinfunction "K_7") (pintype "passive"))
    )
    (net (code "51") (name "Net-(X1H-K)") (class "Default")
      (node (ref "JP3") (pin "1") (pinfunction "1_1") (pintype "passive"))
      (node (ref "X1") (pin "8") (pinfunction "K_8") (pintype "passive"))
      (node (ref "X2") (pin "1") (pinfunction "K_1") (pintype "passive"))
      (node (ref "X2") (pin "3") (pinfunction "K_3") (pintype "passive"))
      (node (ref "X2") (pin "5") (pinfunction "K_5") (pintype "passive"))
    )
    (net (code "52") (name "Net-(X1I-K)") (class "Default")
      (node (ref "R9") (pin "2") (pinfunction "2_2") (pintype "passive"))
      (node (ref "X1") (pin "9") (pinfunction "K_9") (pintype "passive"))
    )
    (net (code "53") (name "Net-(X2B-K)") (class "Default")
      (node (ref "R12") (pin "2") (pinfunction "2_2") (pintype "passive"))
      (node (ref "X2") (pin "2") (pinfunction "K_2") (pintype "passive"))
    )
    (net (code "54") (name "Net-(X2D-K)") (class "Default")
      (node (ref "R15") (pin "2") (pinfunction "2_2") (pintype "passive"))
      (node (ref "X2") (pin "4") (pinfunction "K_4") (pintype "passive"))
    )
    (net (code "55") (name "Net-(X2I-K)") (class "Default")
      (node (ref "JP2") (pin "1") (pinfunction "1_1") (pintype "passive"))
      (node (ref "X2") (pin "9") (pinfunction "K_9") (pintype "passive"))
    )
    (net (code "56") (name "unconnected-(GPS_SE-B-Pad5)") (class "Default")
      (node (ref "GPS_S") (pin "5") (pinfunction "B_5") (pintype "passive"))
    )
    (net (code "57") (name "unconnected-(GPS_SG-B-Pad7)") (class "Default")
      (node (ref "GPS_S") (pin "7") (pinfunction "B_7") (pintype "passive"))
    )
    (net (code "58") (name "unconnected-(IC1-OPT-Pad3)") (class "Default")
      (node (ref "IC1") (pin "3") (pinfunction "OPT_3") (pintype "output"))
    )
    (net (code "59") (name "unconnected-(IC1-TRM-Pad5)") (class "Default")
      (node (ref "IC1") (pin "5") (pinfunction "TRM_5") (pintype "input"))
    )
    (net (code "60") (name "unconnected-(IC5A-QA-Pad15)") (class "Default")
      (node (ref "IC5") (pin "15") (pinfunction "QA_15") (pintype "tri_state"))
    )
    (net (code "61") (name "unconnected-(IC5A-QB-Pad1)") (class "Default")
      (node (ref "IC5") (pin "1") (pinfunction "QB_1") (pintype "tri_state"))
    )
    (net (code "62") (name "unconnected-(IC5A-QC-Pad2)") (class "Default")
      (node (ref "IC5") (pin "2") (pinfunction "QC_2") (pintype "tri_state"))
    )
    (net (code "63") (name "unconnected-(IC5A-QD-Pad3)") (class "Default")
      (node (ref "IC5") (pin "3") (pinfunction "QD_3") (pintype "tri_state"))
    )
    (net (code "64") (name "unconnected-(IC5A-QE-Pad4)") (class "Default")
      (node (ref "IC5") (pin "4") (pinfunction "QE_4") (pintype "tri_state"))
    )
    (net (code "65") (name "unconnected-(IC5A-QH-Pad7)") (class "Default")
      (node (ref "IC5") (pin "7") (pinfunction "QH_7") (pintype "tri_state"))
    )
    (net (code "66") (name "unconnected-(IC5A-RCO-Pad9)") (class "Default")
      (node (ref "IC5") (pin "9") (pinfunction "RCO_9") (pintype "output"))
    )
    (net (code "67") (name "unconnected-(IC6A-2A-Pad5)") (class "Default")
      (node (ref "IC6") (pin "5") (pinfunction "2A_5") (pintype "input"))
    )
    (net (code "68") (name "unconnected-(IC6A-2B-Pad6)") (class "Default")
      (node (ref "IC6") (pin "6") (pinfunction "2B_6") (pintype "input"))
    )
    (net (code "69") (name "unconnected-(IC6A-2Y-Pad7)") (class "Default")
      (node (ref "IC6") (pin "7") (pinfunction "2Y_7") (pintype "output"))
    )
    (net (code "70") (name "unconnected-(IC6A-3A-Pad11)") (class "Default")
      (node (ref "IC6") (pin "11") (pinfunction "3A_11") (pintype "input"))
    )
    (net (code "71") (name "unconnected-(IC6A-3B-Pad10)") (class "Default")
      (node (ref "IC6") (pin "10") (pinfunction "3B_10") (pintype "input"))
    )
    (net (code "72") (name "unconnected-(IC6A-3Y-Pad9)") (class "Default")
      (node (ref "IC6") (pin "9") (pinfunction "3Y_9") (pintype "output"))
    )
    (net (code "73") (name "unconnected-(IC6A-4A-Pad14)") (class "Default")
      (node (ref "IC6") (pin "14") (pinfunction "4A_14") (pintype "input"))
    )
    (net (code "74") (name "unconnected-(IC6A-4B-Pad13)") (class "Default")
      (node (ref "IC6") (pin "13") (pinfunction "4B_13") (pintype "input"))
    )
    (net (code "75") (name "unconnected-(IC6A-4Y-Pad12)") (class "Default")
      (node (ref "IC6") (pin "12") (pinfunction "4Y_12") (pintype "output"))
    )
    (net (code "76") (name "unconnected-(IC7A-AINN5-Pad52)") (class "Default")
      (node (ref "IC7") (pin "52") (pinfunction "AINN5_52") (pintype "input"))
    )
    (net (code "77") (name "unconnected-(IC7A-AINN6-Pad50)") (class "Default")
      (node (ref "IC7") (pin "50") (pinfunction "AINN6_50") (pintype "input"))
    )
    (net (code "78") (name "unconnected-(IC7A-AINN7-Pad48)") (class "Default")
      (node (ref "IC7") (pin "48") (pinfunction "AINN7_48") (pintype "input"))
    )
    (net (code "79") (name "unconnected-(IC7A-AINN8-Pad46)") (class "Default")
      (node (ref "IC7") (pin "46") (pinfunction "AINN8_46") (pintype "input"))
    )
    (net (code "80") (name "unconnected-(IC7A-AINP5-Pad51)") (class "Default")
      (node (ref "IC7") (pin "51") (pinfunction "AINP5_51") (pintype "input"))
    )
    (net (code "81") (name "unconnected-(IC7A-AINP6-Pad49)") (class "Default")
      (node (ref "IC7") (pin "49") (pinfunction "AINP6_49") (pintype "input"))
    )
    (net (code "82") (name "unconnected-(IC7A-AINP7-Pad47)") (class "Default")
      (node (ref "IC7") (pin "47") (pinfunction "AINP7_47") (pintype "input"))
    )
    (net (code "83") (name "unconnected-(IC7A-AINP8-Pad45)") (class "Default")
      (node (ref "IC7") (pin "45") (pinfunction "AINP8_45") (pintype "input"))
    )
    (net (code "84") (name "unconnected-(IC7A-DOUT2-Pad19)") (class "Default")
      (node (ref "IC7") (pin "19") (pinfunction "DOUT2_19") (pintype "output"))
    )
    (net (code "85") (name "unconnected-(IC7A-DOUT3-Pad18)") (class "Default")
      (node (ref "IC7") (pin "18") (pinfunction "DOUT3_18") (pintype "output"))
    )
    (net (code "86") (name "unconnected-(IC7A-DOUT4-Pad17)") (class "Default")
      (node (ref "IC7") (pin "17") (pinfunction "DOUT4_17") (pintype "output"))
    )
    (net (code "87") (name "unconnected-(IC7A-DOUT5-Pad16)") (class "Default")
      (node (ref "IC7") (pin "16") (pinfunction "DOUT5_16") (pintype "output"))
    )
    (net (code "88") (name "unconnected-(IC7A-DOUT6-Pad15)") (class "Default")
      (node (ref "IC7") (pin "15") (pinfunction "DOUT6_15") (pintype "output"))
    )
    (net (code "89") (name "unconnected-(IC7A-DOUT7-Pad14)") (class "Default")
      (node (ref "IC7") (pin "14") (pinfunction "DOUT7_14") (pintype "output"))
    )
    (net (code "90") (name "unconnected-(IC7A-DOUT8-Pad13)") (class "Default")
      (node (ref "IC7") (pin "13") (pinfunction "DOUT8_13") (pintype "output"))
    )
    (net (code "91") (name "unconnected-(IC7A-VCOM-Pad55)") (class "Default")
      (node (ref "IC7") (pin "55") (pinfunction "VCOM_55") (pintype "output"))
    )
    (net (code "92") (name "unconnected-(TS7500-Pad1)") (class "Default")
      (node (ref "TS7500") (pin "1") (pinfunction "1_1") (pintype "passive"))
    )
    (net (code "93") (name "unconnected-(TS7500AE-1-Pad37)") (class "Default")
      (node (ref "TS7500") (pin "37") (pinfunction "1_37") (pintype "passive"))
    )
    (net (code "94") (name "unconnected-(TS7500AF-1-Pad38)") (class "Default")
      (node (ref "TS7500") (pin "38") (pinfunction "1_38") (pintype "passive"))
    )
    (net (code "95") (name "unconnected-(TS7500AG-1-Pad39)") (class "Default")
      (node (ref "TS7500") (pin "39") (pinfunction "1_39") (pintype "passive"))
    )
    (net (code "96") (name "unconnected-(TS7500AH-1-Pad4)") (class "Default")
      (node (ref "TS7500") (pin "4") (pinfunction "1_4") (pintype "passive"))
    )
    (net (code "97") (name "unconnected-(TS7500AI-1-Pad40)") (class "Default")
      (node (ref "TS7500") (pin "40") (pinfunction "1_40") (pintype "passive"))
    )
    (net (code "98") (name "unconnected-(TS7500AJ-1-Pad41)") (class "Default")
      (node (ref "TS7500") (pin "41") (pinfunction "1_41") (pintype "passive"))
    )
    (net (code "99") (name "unconnected-(TS7500AK-1-Pad42)") (class "Default")
      (node (ref "TS7500") (pin "42") (pinfunction "1_42") (pintype "passive"))
    )
    (net (code "100") (name "unconnected-(TS7500AL-1-Pad43)") (class "Default")
      (node (ref "TS7500") (pin "43") (pinfunction "1_43") (pintype "passive"))
    )
    (net (code "101") (name "unconnected-(TS7500AM-1-Pad44)") (class "Default")
      (node (ref "TS7500") (pin "44") (pinfunction "1_44") (pintype "passive"))
    )
    (net (code "102") (name "unconnected-(TS7500AQ-1-Pad8)") (class "Default")
      (node (ref "TS7500") (pin "8") (pinfunction "1_8") (pintype "passive"))
    )
    (net (code "103") (name "unconnected-(TS7500AR-1-Pad9)") (class "Default")
      (node (ref "TS7500") (pin "9") (pinfunction "1_9") (pintype "passive"))
    )
    (net (code "104") (name "unconnected-(TS7500C-1-Pad11)") (class "Default")
      (node (ref "TS7500") (pin "11") (pinfunction "1_11") (pintype "passive"))
    )
    (net (code "105") (name "unconnected-(TS7500E-1-Pad13)") (class "Default")
      (node (ref "TS7500") (pin "13") (pinfunction "1_13") (pintype "passive"))
    )
    (net (code "106") (name "unconnected-(TS7500K-1-Pad19)") (class "Default")
      (node (ref "TS7500") (pin "19") (pinfunction "1_19") (pintype "passive"))
    )
    (net (code "107") (name "unconnected-(TS7500L-1-Pad2)") (class "Default")
      (node (ref "TS7500") (pin "2") (pinfunction "1_2") (pintype "passive"))
    )
    (net (code "108") (name "unconnected-(TS7500M-1-Pad20)") (class "Default")
      (node (ref "TS7500") (pin "20") (pinfunction "1_20") (pintype "passive"))
    )
    (net (code "109") (name "unconnected-(TS7500N-1-Pad21)") (class "Default")
      (node (ref "TS7500") (pin "21") (pinfunction "1_21") (pintype "passive"))
    )
    (net (code "110") (name "unconnected-(TS7500O-1-Pad22)") (class "Default")
      (node (ref "TS7500") (pin "22") (pinfunction "1_22") (pintype "passive"))
    )
    (net (code "111") (name "unconnected-(TS7500P-1-Pad23)") (class "Default")
      (node (ref "TS7500") (pin "23") (pinfunction "1_23") (pintype "passive"))
    )
    (net (code "112") (name "unconnected-(TS7500Q-1-Pad24)") (class "Default")
      (node (ref "TS7500") (pin "24") (pinfunction "1_24") (pintype "passive"))
    )
    (net (code "113") (name "unconnected-(TS7500R-1-Pad25)") (class "Default")
      (node (ref "TS7500") (pin "25") (pinfunction "1_25") (pintype "passive"))
    )
    (net (code "114") (name "unconnected-(TS7500T-1-Pad27)") (class "Default")
      (node (ref "TS7500") (pin "27") (pinfunction "1_27") (pintype "passive"))
    )
    (net (code "115") (name "unconnected-(TS7500U-1-Pad28)") (class "Default")
      (node (ref "TS7500") (pin "28") (pinfunction "1_28") (pintype "passive"))
    )
    (net (code "116") (name "unconnected-(TS7500V-1-Pad29)") (class "Default")
      (node (ref "TS7500") (pin "29") (pinfunction "1_29") (pintype "passive"))
    )
    (net (code "117") (name "unconnected-(TS7500W-1-Pad3)") (class "Default")
      (node (ref "TS7500") (pin "3") (pinfunction "1_3") (pintype "passive"))
    )
    (net (code "118") (name "unconnected-(TS7500X-1-Pad30)") (class "Default")
      (node (ref "TS7500") (pin "30") (pinfunction "1_30") (pintype "passive"))
    )
    (net (code "119") (name "unconnected-(TS7500Y-1-Pad31)") (class "Default")
      (node (ref "TS7500") (pin "31") (pinfunction "1_31") (pintype "passive"))
    )
    (net (code "120") (name "unconnected-(USBB-PadVBUS)") (class "Default")
      (node (ref "USBB") (pin "VBUS") (pinfunction "VBUS_VBUS") (pintype "bidirectional"))
    )
  )
)
